# bottom_board.net
KiCad netlist of a schematic drawn in Altium Designer
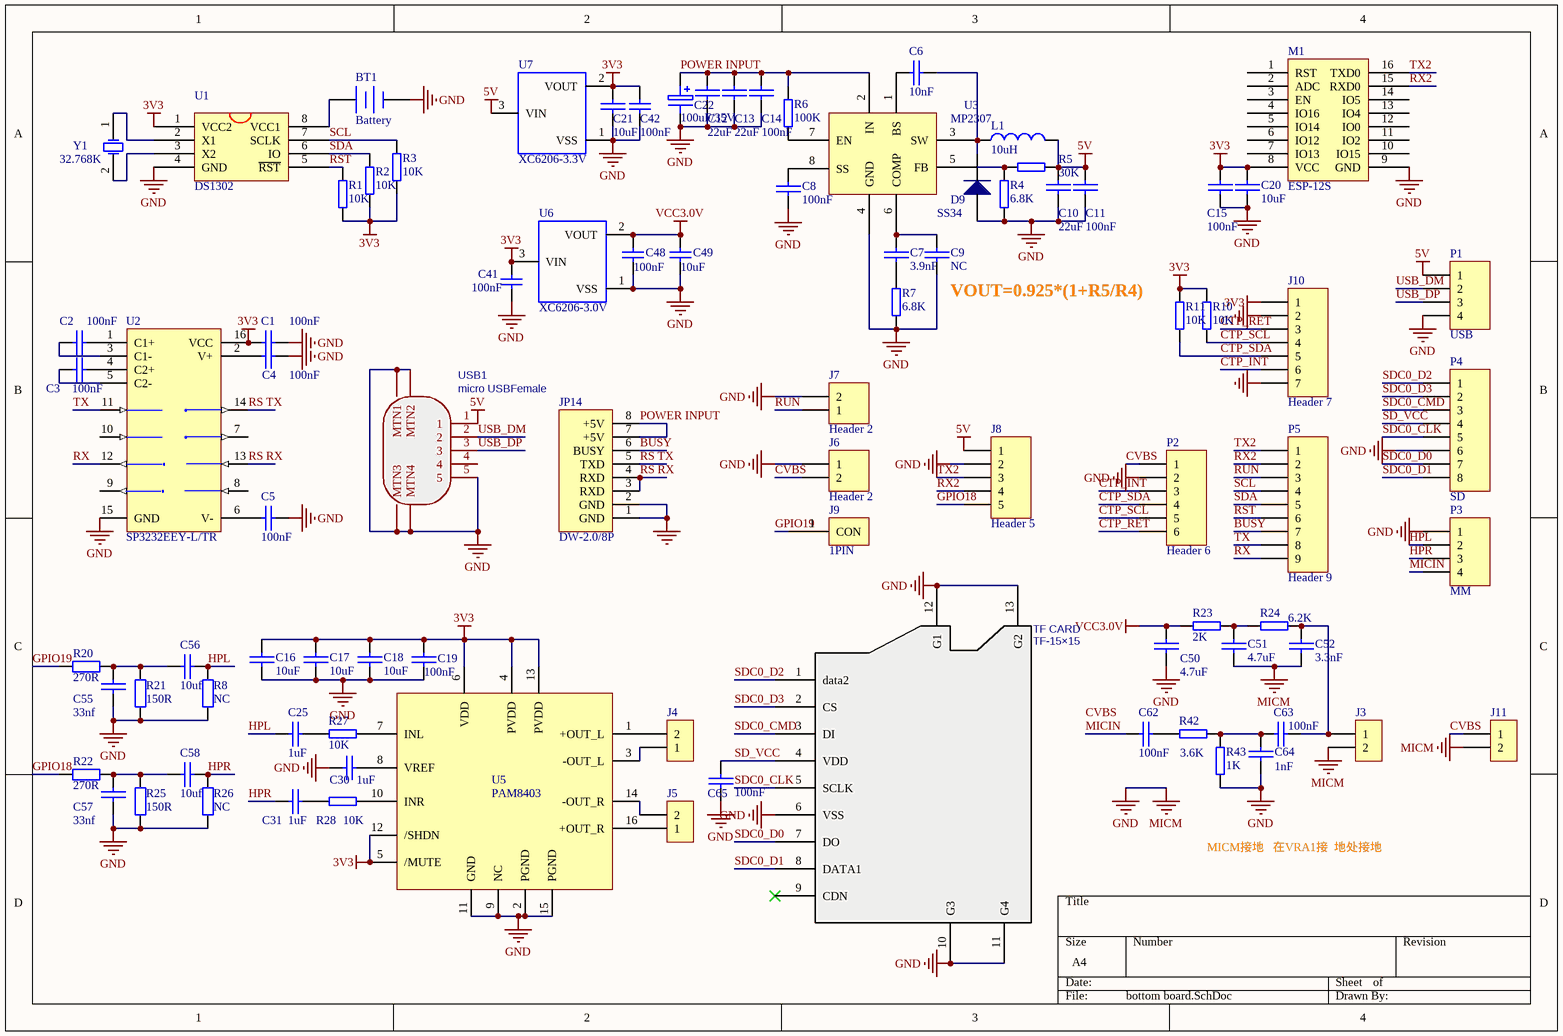
[diagram p0: bottom board.SchDoc]

(export (version "E")
  (design (tool "Eeschema 10.0.6"))
  (components
    (comp (ref "BT1")
      (value "Battery")
      (footprint "My Library:CR1220")
      (description "Multicell Battery")
      (fields (field (name "PUBLISHER") "Altium Limited"))
      (libsource (lib "Miscellaneous Devices") (part "Battery"))
    )
    (comp (ref "C1")
      (value "100nF")
      (footprint "My Library:0603")
      (description "Capacitor")
      (libsource (lib "Devices") (part "CAP"))
    )
    (comp (ref "C2")
      (value "100nF")
      (footprint "My Library:0603")
      (description "Capacitor")
      (libsource (lib "Devices") (part "CAP"))
    )
    (comp (ref "C3")
      (value "100nF")
      (footprint "My Library:0603")
      (description "Capacitor")
      (libsource (lib "Devices") (part "CAP"))
    )
    (comp (ref "C4")
      (value "100nF")
      (footprint "My Library:0603")
      (description "Capacitor")
      (libsource (lib "Devices") (part "CAP"))
    )
    (comp (ref "C5")
      (value "100nF")
      (footprint "My Library:0603")
      (description "Capacitor")
      (libsource (lib "Devices") (part "CAP"))
    )
    (comp (ref "C6")
      (value "10nF")
      (footprint "My Library:0805")
      (description "Capacitor")
      (libsource (lib "Devices") (part "CAP"))
    )
    (comp (ref "C7")
      (value "3.9nF")
      (footprint "My Library:0603")
      (description "Capacitor")
      (libsource (lib "Devices") (part "CAP"))
    )
    (comp (ref "C8")
      (value "100nF")
      (footprint "My Library:0603")
      (description "Capacitor")
      (libsource (lib "Devices") (part "CAP"))
    )
    (comp (ref "C9")
      (value "NC")
      (footprint "My Library:0603")
      (description "Capacitor")
      (libsource (lib "Devices") (part "CAP"))
    )
    (comp (ref "C10")
      (value "22uF")
      (footprint "My Library:0805")
      (description "Capacitor")
      (libsource (lib "Devices") (part "CAP"))
    )
    (comp (ref "C11")
      (value "100nF")
      (footprint "My Library:0603")
      (description "Capacitor")
      (libsource (lib "Devices") (part "CAP"))
    )
    (comp (ref "C12")
      (value "22uF")
      (footprint "My Library:0805")
      (description "Capacitor")
      (libsource (lib "Devices") (part "CAP"))
    )
    (comp (ref "C13")
      (value "22uF")
      (footprint "My Library:0805")
      (description "Capacitor")
      (libsource (lib "Devices") (part "CAP"))
    )
    (comp (ref "C14")
      (value "100nF")
      (footprint "My Library:0603")
      (description "Capacitor")
      (libsource (lib "Devices") (part "CAP"))
    )
    (comp (ref "C15")
      (value "100nF")
      (footprint "My Library:0603")
      (description "Capacitor")
      (libsource (lib "Devices") (part "CAP"))
    )
    (comp (ref "C16")
      (value "10uF")
      (footprint "0603")
      (description "Capacitor")
      (libsource (lib "Devices") (part "CAP"))
    )
    (comp (ref "C17")
      (value "10uF")
      (footprint "0603")
      (description "Capacitor")
      (libsource (lib "Devices") (part "CAP"))
    )
    (comp (ref "C18")
      (value "10uF")
      (footprint "My Library:0603")
      (description "Capacitor")
      (libsource (lib "Devices") (part "CAP"))
    )
    (comp (ref "C19")
      (value "100nF")
      (footprint "My Library:0603")
      (description "Capacitor")
      (libsource (lib "Devices") (part "CAP"))
    )
    (comp (ref "C20")
      (value "10uF")
      (footprint "My Library:0603")
      (description "Capacitor")
      (libsource (lib "Devices") (part "CAP"))
    )
    (comp (ref "C21")
      (value "10uF")
      (footprint "My Library:0603")
      (description "Capacitor")
      (libsource (lib "Devices") (part "CAP"))
    )
    (comp (ref "C22")
      (value "100uF/35V")
      (footprint "My Library:CAP_SMD_6.5MM")
      (libsource (lib "*") (part "ELECTRO1_W"))
    )
    (comp (ref "C25")
      (value "1uF")
      (footprint "My Library:0603")
      (description "Capacitor")
      (libsource (lib "Devices") (part "CAP"))
    )
    (comp (ref "C30")
      (value "1uF")
      (footprint "My Library:0603")
      (description "Capacitor")
      (libsource (lib "Devices") (part "CAP"))
    )
    (comp (ref "C31")
      (value "1uF")
      (footprint "My Library:0603")
      (description "Capacitor")
      (libsource (lib "Devices") (part "CAP"))
    )
    (comp (ref "C41")
      (value "100nF")
      (footprint "0603")
      (description "Capacitor")
      (fields (field (name "PUBLISHER") "Altium Limited"))
      (libsource (lib "Miscellaneous Devices") (part "Cap"))
    )
    (comp (ref "C42")
      (value "100nF")
      (footprint "0603")
      (description "Capacitor")
      (fields (field (name "PUBLISHER") "Altium Limited"))
      (libsource (lib "Miscellaneous Devices") (part "Cap"))
    )
    (comp (ref "C48")
      (value "100nF")
      (footprint "0603")
      (description "Capacitor")
      (fields (field (name "PUBLISHER") "Altium Limited"))
      (libsource (lib "Miscellaneous Devices") (part "Cap"))
    )
    (comp (ref "C49")
      (value "10uF")
      (footprint "0603")
      (description "Capacitor")
      (fields (field (name "PUBLISHER") "Altium Limited"))
      (libsource (lib "Miscellaneous Devices") (part "Cap"))
    )
    (comp (ref "C50")
      (value "4.7uF")
      (footprint "My Library:0603")
      (description "Capacitor")
      (libsource (lib "Devices") (part "CAP"))
    )
    (comp (ref "C51")
      (value "4.7uF")
      (footprint "My Library:0603")
      (description "Capacitor")
      (libsource (lib "Devices") (part "CAP"))
    )
    (comp (ref "C52")
      (value "3.3nF")
      (footprint "My Library:0603")
      (description "Capacitor")
      (libsource (lib "Devices") (part "CAP"))
    )
    (comp (ref "C55") (value "33nf") (footprint "0603") (libsource (lib "*") (part "CAP_W")))
    (comp (ref "C56") (value "10uf") (footprint "0603") (libsource (lib "") (part "CAP_W_1")))
    (comp (ref "C57") (value "33nf") (footprint "0603") (libsource (lib "*") (part "CAP_W")))
    (comp (ref "C58") (value "10uf") (footprint "0603") (libsource (lib "") (part "CAP_W_1")))
    (comp (ref "C62")
      (value "100nF")
      (footprint "My Library:0603")
      (description "Capacitor")
      (libsource (lib "Devices") (part "CAP"))
    )
    (comp (ref "C63")
      (value "100nF")
      (footprint "0603")
      (description "Capacitor")
      (libsource (lib "Devices") (part "CAP"))
    )
    (comp (ref "C64")
      (value "1nF")
      (footprint "My Library:0603")
      (description "Capacitor")
      (libsource (lib "Devices") (part "CAP"))
    )
    (comp (ref "C65")
      (value "100nF")
      (footprint "My Library:0603")
      (description "Capacitor")
      (libsource (lib "Devices") (part "CAP"))
    )
    (comp (ref "D9")
      (value "SS34")
      (footprint "My Library:SMA")
      (description "Diode")
      (libsource (lib "SchlibNode") (part "Diode"))
    )
    (comp (ref "J3")
      (value "~")
      (footprint "My Library:2PIN2.54-SMD")
      (description "Connector")
      (libsource (lib "") (part "CON2_1"))
    )
    (comp (ref "J4")
      (value "~")
      (footprint "My Library:2PIN2.54-SMD")
      (description "Connector")
      (libsource (lib "Devices") (part "CON2"))
    )
    (comp (ref "J5")
      (value "~")
      (footprint "My Library:2PIN2.54-SMD")
      (description "Connector")
      (libsource (lib "Devices") (part "CON2"))
    )
    (comp (ref "J6")
      (value "Header 2")
      (footprint "HDR1X2")
      (description "Header, 2-Pin")
      (fields (field (name "PUBLISHER") "Altium Limited"))
      (libsource (lib "Miscellaneous Connectors") (part "Header 2"))
    )
    (comp (ref "J7")
      (value "Header 2")
      (footprint "HDR1X2")
      (description "Header, 2-Pin")
      (fields (field (name "PUBLISHER") "Altium Limited"))
      (libsource (lib "") (part "Header 2_1"))
    )
    (comp (ref "J8")
      (value "Header 5")
      (footprint "HDR1X5")
      (description "Header, 5-Pin")
      (fields (field (name "PUBLISHER") "Altium Limited"))
      (libsource (lib "Miscellaneous Connectors") (part "Header 5"))
    )
    (comp (ref "J9")
      (value "1PIN")
      (footprint "My Library:1PIN")
      (libsource (lib "My Library") (part "1PIN"))
    )
    (comp (ref "J10")
      (value "Header 7")
      (footprint "My Library:FPC-6PIN")
      (description "Header, 7-Pin")
      (fields (field (name "PUBLISHER") "Altium Limited"))
      (libsource (lib "Miscellaneous Connectors") (part "Header 7"))
    )
    (comp (ref "J11")
      (value "~")
      (footprint "My Library:2PIN2.54-SMD")
      (description "Connector")
      (libsource (lib "") (part "CON2_1"))
    )
    (comp (ref "JP14")
      (value "DW-2.0/8P")
      (footprint "My Library:DW2.0-8P-SMD")
      (libsource (lib "Socket") (part "DW-2.0/8P"))
    )
    (comp (ref "L1")
      (value "10uH")
      (footprint "My Library:LS8")
      (description "Inductor")
      (fields (field (name "PUBLISHER") "Altium Limited"))
      (libsource (lib "Miscellaneous Devices") (part "Inductor"))
    )
    (comp (ref "M1")
      (value "ESP-12S")
      (footprint "My Library:ESP-12S")
      (libsource (lib "My Library") (part "ESP-12S"))
    )
    (comp (ref "P1")
      (value "USB")
      (footprint "My Library:4PIN1.27")
      (description "Header, 4-Pin")
      (fields (field (name "PUBLISHER") "Altium Limited"))
      (libsource (lib "Miscellaneous Connectors") (part "Header 4"))
    )
    (comp (ref "P2")
      (value "Header 6")
      (footprint "My Library:6PIN1.27")
      (description "Header, 6-Pin")
      (fields (field (name "PUBLISHER") "Altium Limited"))
      (libsource (lib "Miscellaneous Connectors") (part "Header 6"))
    )
    (comp (ref "P3")
      (value "MM")
      (footprint "My Library:4PIN1.27")
      (description "Header, 4-Pin")
      (fields (field (name "PUBLISHER") "Altium Limited"))
      (libsource (lib "Miscellaneous Connectors") (part "Header 4"))
    )
    (comp (ref "P4")
      (value "SD")
      (footprint "My Library:8PIN1.27")
      (description "Header, 8-Pin")
      (fields (field (name "PUBLISHER") "Altium Limited"))
      (libsource (lib "Miscellaneous Connectors") (part "Header 8"))
    )
    (comp (ref "P5")
      (value "Header 9")
      (footprint "My Library:9PIN1.27")
      (description "Header, 9-Pin")
      (fields (field (name "PUBLISHER") "Altium Limited"))
      (libsource (lib "Miscellaneous Connectors") (part "Header 9"))
    )
    (comp (ref "R1") (value "10K") (footprint "0603") (libsource (lib "Devices") (part "RES2")))
    (comp (ref "R2") (value "10K") (footprint "0603") (libsource (lib "Devices") (part "RES2")))
    (comp (ref "R3") (value "10K") (footprint "0603") (libsource (lib "Devices") (part "RES2")))
    (comp (ref "R4") (value "6.8K") (footprint "0603") (libsource (lib "Devices") (part "RES2")))
    (comp (ref "R5") (value "30K") (footprint "0603") (libsource (lib "") (part "RES2_1")))
    (comp (ref "R6") (value "100K") (footprint "0603") (libsource (lib "Devices") (part "RES2")))
    (comp (ref "R7") (value "6.8K") (footprint "0603") (libsource (lib "Devices") (part "RES2")))
    (comp (ref "R8")
      (value "NC")
      (footprint "My Library:0603")
      (description "Resistor")
      (fields (field (name "PUBLISHER") "Altium Limited"))
      (libsource (lib "Miscellaneous Devices") (part "Res2"))
    )
    (comp (ref "R10") (value "10K") (footprint "0603") (libsource (lib "Devices") (part "RES2")))
    (comp (ref "R11") (value "10K") (footprint "0603") (libsource (lib "Devices") (part "RES2")))
    (comp (ref "R20")
      (value "270R")
      (footprint "My Library:0603")
      (description "Resistor")
      (fields (field (name "PUBLISHER") "Altium Limited"))
      (libsource (lib "") (part "Res2_1"))
    )
    (comp (ref "R21")
      (value "150R")
      (footprint "My Library:0603")
      (description "Resistor")
      (fields (field (name "PUBLISHER") "Altium Limited"))
      (libsource (lib "") (part "Res2_2"))
    )
    (comp (ref "R22")
      (value "270R")
      (footprint "My Library:0603")
      (description "Resistor")
      (fields (field (name "PUBLISHER") "Altium Limited"))
      (libsource (lib "") (part "Res2_3"))
    )
    (comp (ref "R23") (value "2K") (footprint "0603") (libsource (lib "") (part "RES2_1")))
    (comp (ref "R24") (value "6.2K") (footprint "0603") (libsource (lib "") (part "RES2_1")))
    (comp (ref "R25")
      (value "150R")
      (footprint "My Library:0603")
      (description "Resistor")
      (fields (field (name "PUBLISHER") "Altium Limited"))
      (libsource (lib "Miscellaneous Devices") (part "Res2"))
    )
    (comp (ref "R26")
      (value "NC")
      (footprint "My Library:0603")
      (description "Resistor")
      (fields (field (name "PUBLISHER") "Altium Limited"))
      (libsource (lib "Miscellaneous Devices") (part "Res2"))
    )
    (comp (ref "R27") (value "10K") (footprint "0603") (libsource (lib "Devices") (part "RES2")))
    (comp (ref "R28") (value "10K") (footprint "0603") (libsource (lib "Devices") (part "RES2")))
    (comp (ref "R42") (value "3.6K") (footprint "0603") (libsource (lib "Devices") (part "RES2")))
    (comp (ref "R43") (value "1K") (footprint "0603") (libsource (lib "Devices") (part "RES2")))
    (comp (ref "TF CARD")
      (value "TF-15×15")
      (footprint "My Library:SD_MICRO")
      (fields (field (name "BOM_SUPPLIER PART") "C111196"))
      (libsource (lib "My Library") (part "TF-15×15"))
    )
    (comp (ref "U1") (value "DS1302") (footprint "SOP-8") (libsource (lib "My Library") (part "DS1302")))
    (comp (ref "U2")
      (value "SP3232EEY-L/TR")
      (footprint "My Library:SOIC-16")
      (description "RS232")
      (libsource (lib "IC") (part "SP3232EEY-L/TR"))
    )
    (comp (ref "U3")
      (value "MP2307")
      (footprint "My Library:SOP-8")
      (libsource (lib "My Library") (part "MP2307"))
    )
    (comp (ref "U5") (value "PAM8403") (footprint "SOIC-16") (libsource (lib "Devices") (part "SC8403")))
    (comp (ref "U6") (value "XC6206-3.0V") (footprint "SOT-23-3") (libsource (lib "PCBLIB") (part "XC6206")))
    (comp (ref "U7") (value "XC6206-3.3V") (footprint "SOT-23-3") (libsource (lib "PCBLIB") (part "XC6206")))
    (comp (ref "USB1")
      (value "micro USBFemale")
      (footprint "USB_MICRO")
      (fields (field (name "BOM_SUPPLIER PART") "C10418"))
      (libsource (lib "My Library") (part "micro USBFemale"))
    )
    (comp (ref "Y1")
      (value "32.768K")
      (footprint "My Library:SMD-3215")
      (description "Crystal Oscillator")
      (fields (field (name "PUBLISHER") "Altium Limited"))
      (libsource (lib "Miscellaneous Devices") (part "XTAL"))
    )
  )
  (nets
    (net (code "1") (name "/BUSY") (class "Default")
      (node (ref "JP14") (pin "6") (pinfunction "BUSY_6") (pintype "passive"))
      (node (ref "P5") (pin "7") (pinfunction "7_7") (pintype "passive"))
    )
    (net (code "2") (name "/CTP_INT") (class "Default")
      (node (ref "J10") (pin "6") (pinfunction "6_6") (pintype "passive"))
      (node (ref "P2") (pin "3") (pinfunction "3_3") (pintype "passive"))
    )
    (net (code "3") (name "/CTP_RET") (class "Default")
      (node (ref "J10") (pin "3") (pinfunction "3_3") (pintype "passive"))
      (node (ref "P2") (pin "6") (pinfunction "6_6") (pintype "passive"))
    )
    (net (code "4") (name "/CTP_SCL") (class "Default")
      (node (ref "J10") (pin "4") (pinfunction "4_4") (pintype "passive"))
      (node (ref "P2") (pin "5") (pinfunction "5_5") (pintype "passive"))
      (node (ref "R10") (pin "2") (pinfunction "2_2") (pintype "passive"))
    )
    (net (code "5") (name "/CTP_SDA") (class "Default")
      (node (ref "J10") (pin "5") (pinfunction "5_5") (pintype "passive"))
      (node (ref "P2") (pin "4") (pinfunction "4_4") (pintype "passive"))
      (node (ref "R11") (pin "2") (pinfunction "2_2") (pintype "passive"))
    )
    (net (code "6") (name "/CVBS") (class "Default")
      (node (ref "J11") (pin "1") (pinfunction "1_1") (pintype "passive"))
      (node (ref "J6") (pin "2") (pinfunction "2_2") (pintype "passive"))
      (node (ref "P2") (pin "1") (pinfunction "1_1") (pintype "passive"))
    )
    (net (code "7") (name "/GPIO18") (class "Default")
      (node (ref "J8") (pin "5") (pinfunction "5_5") (pintype "passive"))
      (node (ref "R22") (pin "1") (pinfunction "1_1") (pintype "passive"))
    )
    (net (code "8") (name "/GPIO19") (class "Default")
      (node (ref "J9") (pin "1") (pinfunction "CON_1") (pintype "passive"))
      (node (ref "R20") (pin "2") (pinfunction "2_2") (pintype "passive"))
    )
    (net (code "9") (name "/HPL") (class "Default")
      (node (ref "C25") (pin "2") (pinfunction "2_2") (pintype "passive"))
      (node (ref "C56") (pin "1") (pinfunction "1_1") (pintype "passive"))
      (node (ref "P3") (pin "2") (pinfunction "2_2") (pintype "passive"))
      (node (ref "R8") (pin "2") (pinfunction "2_2") (pintype "passive"))
    )
    (net (code "10") (name "/HPR") (class "Default")
      (node (ref "C31") (pin "2") (pinfunction "2_2") (pintype "passive"))
      (node (ref "C58") (pin "1") (pinfunction "1_1") (pintype "passive"))
      (node (ref "P3") (pin "3") (pinfunction "3_3") (pintype "passive"))
      (node (ref "R26") (pin "2") (pinfunction "2_2") (pintype "passive"))
    )
    (net (code "11") (name "/MICIN") (class "Default")
      (node (ref "C62") (pin "1") (pinfunction "1_1") (pintype "passive"))
      (node (ref "P3") (pin "4") (pinfunction "4_4") (pintype "passive"))
    )
    (net (code "12") (name "/POWER INPUT") (class "Default")
      (node (ref "C12") (pin "1") (pinfunction "1_1") (pintype "passive"))
      (node (ref "C13") (pin "1") (pinfunction "1_1") (pintype "passive"))
      (node (ref "C14") (pin "1") (pinfunction "1_1") (pintype "passive"))
      (node (ref "C22") (pin "1") (pinfunction "1_1") (pintype "passive"))
      (node (ref "JP14") (pin "7") (pinfunction "+5V_7") (pintype "passive"))
      (node (ref "JP14") (pin "8") (pinfunction "+5V_8") (pintype "passive"))
      (node (ref "R6") (pin "2") (pinfunction "2_2") (pintype "passive"))
      (node (ref "U3") (pin "2") (pinfunction "IN_2") (pintype "passive"))
    )
    (net (code "13") (name "/RS RX") (class "Default")
      (node (ref "JP14") (pin "3") (pinfunction "RXD_3") (pintype "passive"))
      (node (ref "JP14") (pin "4") (pinfunction "RXD_4") (pintype "passive"))
      (node (ref "U2") (pin "13") (pinfunction "R1IN_13") (pintype "input"))
    )
    (net (code "14") (name "/RS TX") (class "Default")
      (node (ref "JP14") (pin "5") (pinfunction "TXD_5") (pintype "passive"))
      (node (ref "U2") (pin "14") (pinfunction "T1OUT_14") (pintype "output"))
    )
    (net (code "15") (name "/RST") (class "Default")
      (node (ref "P5") (pin "6") (pinfunction "6_6") (pintype "passive"))
      (node (ref "R1") (pin "2") (pinfunction "2_2") (pintype "passive"))
      (node (ref "U1") (pin "5") (pinfunction "~{RST}_5") (pintype "passive"))
    )
    (net (code "16") (name "/RUN") (class "Default")
      (node (ref "J7") (pin "1") (pinfunction "1_1") (pintype "passive"))
      (node (ref "P5") (pin "3") (pinfunction "3_3") (pintype "passive"))
    )
    (net (code "17") (name "/RX") (class "Default")
      (node (ref "P5") (pin "9") (pinfunction "9_9") (pintype "passive"))
      (node (ref "U2") (pin "12") (pinfunction "R1OUT_12") (pintype "output"))
    )
    (net (code "18") (name "/RX2") (class "Default")
      (node (ref "J8") (pin "4") (pinfunction "4_4") (pintype "passive"))
      (node (ref "M1") (pin "15") (pinfunction "RXD0_15") (pintype "passive"))
      (node (ref "P5") (pin "2") (pinfunction "2_2") (pintype "passive"))
    )
    (net (code "19") (name "/SCL") (class "Default")
      (node (ref "P5") (pin "4") (pinfunction "4_4") (pintype "passive"))
      (node (ref "R3") (pin "1") (pinfunction "1_1") (pintype "passive"))
      (node (ref "U1") (pin "7") (pinfunction "SCLK_7") (pintype "passive"))
    )
    (net (code "20") (name "/SDA") (class "Default")
      (node (ref "P5") (pin "5") (pinfunction "5_5") (pintype "passive"))
      (node (ref "R2") (pin "1") (pinfunction "1_1") (pintype "passive"))
      (node (ref "U1") (pin "6") (pinfunction "IO_6") (pintype "passive"))
    )
    (net (code "21") (name "/SDC0_CLK") (class "Default")
      (node (ref "P4") (pin "5") (pinfunction "5_5") (pintype "passive"))
      (node (ref "TF CARD") (pin "5") (pinfunction "SCLK_5") (pintype "passive"))
    )
    (net (code "22") (name "/SDC0_CMD") (class "Default")
      (node (ref "P4") (pin "3") (pinfunction "3_3") (pintype "passive"))
      (node (ref "TF CARD") (pin "3") (pinfunction "DI_3") (pintype "passive"))
    )
    (net (code "23") (name "/SDC0_D0") (class "Default")
      (node (ref "P4") (pin "7") (pinfunction "7_7") (pintype "passive"))
      (node (ref "TF CARD") (pin "7") (pinfunction "DO_7") (pintype "passive"))
    )
    (net (code "24") (name "/SDC0_D1") (class "Default")
      (node (ref "P4") (pin "8") (pinfunction "8_8") (pintype "passive"))
      (node (ref "TF CARD") (pin "8") (pinfunction "DATA1_8") (pintype "passive"))
    )
    (net (code "25") (name "/SDC0_D2") (class "Default")
      (node (ref "P4") (pin "1") (pinfunction "1_1") (pintype "passive"))
      (node (ref "TF CARD") (pin "1") (pinfunction "data2_1") (pintype "passive"))
    )
    (net (code "26") (name "/SDC0_D3") (class "Default")
      (node (ref "P4") (pin "2") (pinfunction "2_2") (pintype "passive"))
      (node (ref "TF CARD") (pin "2") (pinfunction "CS_2") (pintype "passive"))
    )
    (net (code "27") (name "/SD_VCC") (class "Default")
      (node (ref "C65") (pin "1") (pinfunction "1_1") (pintype "passive"))
      (node (ref "P4") (pin "4") (pinfunction "4_4") (pintype "passive"))
      (node (ref "TF CARD") (pin "4") (pinfunction "VDD_4") (pintype "passive"))
    )
    (net (code "28") (name "/TX") (class "Default")
      (node (ref "P5") (pin "8") (pinfunction "8_8") (pintype "passive"))
      (node (ref "U2") (pin "11") (pinfunction "T1IN_11") (pintype "input"))
    )
    (net (code "29") (name "/TX2") (class "Default")
      (node (ref "J8") (pin "3") (pinfunction "3_3") (pintype "passive"))
      (node (ref "M1") (pin "16") (pinfunction "TXD0_16") (pintype "passive"))
      (node (ref "P5") (pin "1") (pinfunction "1_1") (pintype "passive"))
    )
    (net (code "30") (name "/USB_DM") (class "Default")
      (node (ref "P1") (pin "2") (pinfunction "2_2") (pintype "passive"))
      (node (ref "USB1") (pin "2") (pinfunction "2_2") (pintype "passive"))
    )
    (net (code "31") (name "/USB_DP") (class "Default")
      (node (ref "P1") (pin "3") (pinfunction "3_3") (pintype "passive"))
      (node (ref "USB1") (pin "3") (pinfunction "3_3") (pintype "passive"))
    )
    (net (code "32") (name "3V3") (class "Default")
      (node (ref "C1") (pin "2") (pinfunction "2_2") (pintype "passive"))
      (node (ref "C15") (pin "1") (pinfunction "1_1") (pintype "passive"))
      (node (ref "C16") (pin "1") (pinfunction "1_1") (pintype "passive"))
      (node (ref "C17") (pin "1") (pinfunction "1_1") (pintype "passive"))
      (node (ref "C18") (pin "1") (pinfunction "1_1") (pintype "passive"))
      (node (ref "C19") (pin "2") (pinfunction "2_2") (pintype "passive"))
      (node (ref "C20") (pin "2") (pinfunction "2_2") (pintype "passive"))
      (node (ref "C21") (pin "1") (pinfunction "1_1") (pintype "passive"))
      (node (ref "C41") (pin "1") (pinfunction "1_1") (pintype "passive"))
      (node (ref "C42") (pin "1") (pinfunction "1_1") (pintype "passive"))
      (node (ref "J10") (pin "1") (pinfunction "1_1") (pintype "passive"))
      (node (ref "M1") (pin "8") (pinfunction "VCC_8") (pintype "passive"))
      (node (ref "R1") (pin "1") (pinfunction "1_1") (pintype "passive"))
      (node (ref "R10") (pin "1") (pinfunction "1_1") (pintype "passive"))
      (node (ref "R11") (pin "1") (pinfunction "1_1") (pintype "passive"))
      (node (ref "R2") (pin "2") (pinfunction "2_2") (pintype "passive"))
      (node (ref "R3") (pin "2") (pinfunction "2_2") (pintype "passive"))
      (node (ref "U1") (pin "1") (pinfunction "VCC2_1") (pintype "passive"))
      (node (ref "U2") (pin "16") (pinfunction "VCC_16") (pintype "power_in"))
      (node (ref "U5") (pin "12") (pinfunction "/SHDN_12") (pintype "passive"))
      (node (ref "U5") (pin "13") (pinfunction "PVDD_13") (pintype "passive"))
      (node (ref "U5") (pin "4") (pinfunction "PVDD_4") (pintype "passive"))
      (node (ref "U5") (pin "5") (pinfunction "/MUTE_5") (pintype "passive"))
      (node (ref "U5") (pin "6") (pinfunction "VDD_6") (pintype "passive"))
      (node (ref "U6") (pin "3") (pinfunction "VIN_3") (pintype "passive"))
      (node (ref "U7") (pin "2") (pinfunction "VOUT_2") (pintype "passive"))
    )
    (net (code "33") (name "5V") (class "Default")
      (node (ref "C10") (pin "1") (pinfunction "1_1") (pintype "passive"))
      (node (ref "C11") (pin "1") (pinfunction "1_1") (pintype "passive"))
      (node (ref "J8") (pin "1") (pinfunction "1_1") (pintype "passive"))
      (node (ref "L1") (pin "2") (pinfunction "2_2") (pintype "passive"))
      (node (ref "P1") (pin "1") (pinfunction "1_1") (pintype "passive"))
      (node (ref "R5") (pin "2") (pinfunction "2_2") (pintype "passive"))
      (node (ref "U7") (pin "3") (pinfunction "VIN_3") (pintype "passive"))
      (node (ref "USB1") (pin "1") (pinfunction "1_1") (pintype "passive"))
    )
    (net (code "34") (name "GND") (class "Default")
      (node (ref "BT1") (pin "2") (pinfunction "-_2") (pintype "passive"))
      (node (ref "C1") (pin "1") (pinfunction "1_1") (pintype "passive"))
      (node (ref "C10") (pin "2") (pinfunction "2_2") (pintype "passive"))
      (node (ref "C11") (pin "2") (pinfunction "2_2") (pintype "passive"))
      (node (ref "C12") (pin "2") (pinfunction "2_2") (pintype "passive"))
      (node (ref "C13") (pin "2") (pinfunction "2_2") (pintype "passive"))
      (node (ref "C14") (pin "2") (pinfunction "2_2") (pintype "passive"))
      (node (ref "C15") (pin "2") (pinfunction "2_2") (pintype "passive"))
      (node (ref "C16") (pin "2") (pinfunction "2_2") (pintype "passive"))
      (node (ref "C17") (pin "2") (pinfunction "2_2") (pintype "passive"))
      (node (ref "C18") (pin "2") (pinfunction "2_2") (pintype "passive"))
      (node (ref "C19") (pin "1") (pinfunction "1_1") (pintype "passive"))
      (node (ref "C20") (pin "1") (pinfunction "1_1") (pintype "passive"))
      (node (ref "C21") (pin "2") (pinfunction "2_2") (pintype "passive"))
      (node (ref "C22") (pin "2") (pinfunction "2_2") (pintype "passive"))
      (node (ref "C30") (pin "2") (pinfunction "2_2") (pintype "passive"))
      (node (ref "C4") (pin "2") (pinfunction "2_2") (pintype "passive"))
      (node (ref "C41") (pin "2") (pinfunction "2_2") (pintype "passive"))
      (node (ref "C42") (pin "2") (pinfunction "2_2") (pintype "passive"))
      (node (ref "C48") (pin "2") (pinfunction "2_2") (pintype "passive"))
      (node (ref "C49") (pin "1") (pinfunction "1_1") (pintype "passive"))
      (node (ref "C5") (pin "1") (pinfunction "1_1") (pintype "passive"))
      (node (ref "C50") (pin "2") (pinfunction "2_2") (pintype "passive"))
      (node (ref "C51") (pin "2") (pinfunction "2_2") (pintype "passive"))
      (node (ref "C52") (pin "1") (pinfunction "1_1") (pintype "passive"))
      (node (ref "C55") (pin "1") (pinfunction "1_1") (pintype "passive"))
      (node (ref "C57") (pin "1") (pinfunction "1_1") (pintype "passive"))
      (node (ref "C64") (pin "1") (pinfunction "1_1") (pintype "passive"))
      (node (ref "C65") (pin "2") (pinfunction "2_2") (pintype "passive"))
      (node (ref "C8") (pin "2") (pinfunction "2_2") (pintype "passive"))
      (node (ref "C9") (pin "2") (pinfunction "2_2") (pintype "passive"))
      (node (ref "D9") (pin "1") (pinfunction "A_1") (pintype "passive"))
      (node (ref "J10") (pin "2") (pinfunction "2_2") (pintype "passive"))
      (node (ref "J10") (pin "7") (pinfunction "7_7") (pintype "passive"))
      (node (ref "J11") (pin "2") (pinfunction "2_2") (pintype "passive"))
      (node (ref "J3") (pin "2") (pinfunction "2_2") (pintype "passive"))
      (node (ref "J6") (pin "1") (pinfunction "1_1") (pintype "passive"))
      (node (ref "J7") (pin "2") (pinfunction "2_2") (pintype "passive"))
      (node (ref "J8") (pin "2") (pinfunction "2_2") (pintype "passive"))
      (node (ref "JP14") (pin "1") (pinfunction "GND_1") (pintype "passive"))
      (node (ref "JP14") (pin "2") (pinfunction "GND_2") (pintype "passive"))
      (node (ref "M1") (pin "9") (pinfunction "GND_9") (pintype "passive"))
      (node (ref "P1") (pin "4") (pinfunction "4_4") (pintype "passive"))
      (node (ref "P2") (pin "2") (pinfunction "2_2") (pintype "passive"))
      (node (ref "P3") (pin "1") (pinfunction "1_1") (pintype "passive"))
      (node (ref "P4") (pin "6") (pinfunction "6_6") (pintype "passive"))
      (node (ref "R21") (pin "2") (pinfunction "2_2") (pintype "passive"))
      (node (ref "R25") (pin "1") (pinfunction "1_1") (pintype "passive"))
      (node (ref "R26") (pin "1") (pinfunction "1_1") (pintype "passive"))
      (node (ref "R4") (pin "2") (pinfunction "2_2") (pintype "passive"))
      (node (ref "R43") (pin "1") (pinfunction "1_1") (pintype "passive"))
      (node (ref "R7") (pin "1") (pinfunction "1_1") (pintype "passive"))
      (node (ref "R8") (pin "1") (pinfunction "1_1") (pintype "passive"))
      (node (ref "TF CARD") (pin "10") (pinfunction "G3_10") (pintype "passive"))
      (node (ref "TF CARD") (pin "11") (pinfunction "G4_11") (pintype "passive"))
      (node (ref "TF CARD") (pin "12") (pinfunction "G1_12") (pintype "passive"))
      (node (ref "TF CARD") (pin "13") (pinfunction "G2_13") (pintype "passive"))
      (node (ref "TF CARD") (pin "6") (pinfunction "VSS_6") (pintype "passive"))
      (node (ref "U1") (pin "4") (pinfunction "GND_4") (pintype "passive"))
      (node (ref "U2") (pin "15") (pinfunction "GND_15") (pintype "power_in"))
      (node (ref "U3") (pin "4") (pinfunction "GND_4") (pintype "passive"))
      (node (ref "U5") (pin "11") (pinfunction "GND_11") (pintype "passive"))
      (node (ref "U5") (pin "15") (pinfunction "PGND_15") (pintype "passive"))
      (node (ref "U5") (pin "2") (pinfunction "PGND_2") (pintype "passive"))
      (node (ref "U5") (pin "9") (pinfunction "NC_9") (pintype "passive"))
      (node (ref "U6") (pin "1") (pinfunction "VSS_1") (pintype "passive"))
      (node (ref "U7") (pin "1") (pinfunction "VSS_1") (pintype "passive"))
      (node (ref "USB1") (pin "0") (pinfunction "MTN4_0") (pintype "passive"))
      (node (ref "USB1") (pin "5") (pinfunction "5_5") (pintype "passive"))
    )
    (net (code "35") (name "Net-(BT1-+)") (class "Default")
      (node (ref "BT1") (pin "1") (pinfunction "+_1") (pintype "passive"))
      (node (ref "U1") (pin "8") (pinfunction "VCC1_8") (pintype "passive"))
    )
    (net (code "36") (name "Net-(C7-Pad2)") (class "Default")
      (node (ref "C7") (pin "2") (pinfunction "2_2") (pintype "passive"))
      (node (ref "R7") (pin "2") (pinfunction "2_2") (pintype "passive"))
    )
    (net (code "37") (name "Net-(C25-Pad1)") (class "Default")
      (node (ref "C25") (pin "1") (pinfunction "1_1") (pintype "passive"))
      (node (ref "R27") (pin "2") (pinfunction "2_2") (pintype "passive"))
    )
    (net (code "38") (name "Net-(C31-Pad1)") (class "Default")
      (node (ref "C31") (pin "1") (pinfunction "1_1") (pintype "passive"))
      (node (ref "R28") (pin "2") (pinfunction "2_2") (pintype "passive"))
    )
    (net (code "39") (name "Net-(C51-Pad1)") (class "Default")
      (node (ref "C51") (pin "1") (pinfunction "1_1") (pintype "passive"))
      (node (ref "R23") (pin "1") (pinfunction "1_1") (pintype "passive"))
      (node (ref "R24") (pin "2") (pinfunction "2_2") (pintype "passive"))
    )
    (net (code "40") (name "Net-(C52-Pad2)") (class "Default")
      (node (ref "C52") (pin "2") (pinfunction "2_2") (pintype "passive"))
      (node (ref "C63") (pin "2") (pinfunction "2_2") (pintype "passive"))
      (node (ref "J3") (pin "1") (pinfunction "1_1") (pintype "passive"))
      (node (ref "R24") (pin "1") (pinfunction "1_1") (pintype "passive"))
    )
    (net (code "41") (name "Net-(C55-Pad2)") (class "Default")
      (node (ref "C55") (pin "2") (pinfunction "2_2") (pintype "passive"))
      (node (ref "C56") (pin "2") (pinfunction "2_2") (pintype "passive"))
      (node (ref "R20") (pin "1") (pinfunction "1_1") (pintype "passive"))
      (node (ref "R21") (pin "1") (pinfunction "1_1") (pintype "passive"))
    )
    (net (code "42") (name "Net-(C57-Pad2)") (class "Default")
      (node (ref "C57") (pin "2") (pinfunction "2_2") (pintype "passive"))
      (node (ref "C58") (pin "2") (pinfunction "2_2") (pintype "passive"))
      (node (ref "R22") (pin "2") (pinfunction "2_2") (pintype "passive"))
      (node (ref "R25") (pin "2") (pinfunction "2_2") (pintype "passive"))
    )
    (net (code "43") (name "Net-(C62-Pad2)") (class "Default")
      (node (ref "C62") (pin "2") (pinfunction "2_2") (pintype "passive"))
      (node (ref "R42") (pin "1") (pinfunction "1_1") (pintype "passive"))
    )
    (net (code "44") (name "Net-(C63-Pad1)") (class "Default")
      (node (ref "C63") (pin "1") (pinfunction "1_1") (pintype "passive"))
      (node (ref "C64") (pin "2") (pinfunction "2_2") (pintype "passive"))
      (node (ref "R42") (pin "2") (pinfunction "2_2") (pintype "passive"))
      (node (ref "R43") (pin "2") (pinfunction "2_2") (pintype "passive"))
    )
    (net (code "45") (name "Net-(D9-K)") (class "Default")
      (node (ref "C6") (pin "1") (pinfunction "1_1") (pintype "passive"))
      (node (ref "D9") (pin "2") (pinfunction "K_2") (pintype "passive"))
      (node (ref "L1") (pin "1") (pinfunction "1_1") (pintype "passive"))
      (node (ref "U3") (pin "3") (pinfunction "SW_3") (pintype "passive"))
    )
    (net (code "46") (name "Net-(U1-X1)") (class "Default")
      (node (ref "U1") (pin "2") (pinfunction "X1_2") (pintype "passive"))
      (node (ref "Y1") (pin "1") (pinfunction "OSC1_1") (pintype "passive"))
    )
    (net (code "47") (name "Net-(U1-X2)") (class "Default")
      (node (ref "U1") (pin "3") (pinfunction "X2_3") (pintype "passive"))
      (node (ref "Y1") (pin "2") (pinfunction "OSC2_2") (pintype "passive"))
    )
    (net (code "48") (name "Net-(U2-C1+)") (class "Default")
      (node (ref "C2") (pin "1") (pinfunction "1_1") (pintype "passive"))
      (node (ref "U2") (pin "1") (pinfunction "C1+_1") (pintype "passive"))
    )
    (net (code "49") (name "Net-(U2-C1-)") (class "Default")
      (node (ref "C2") (pin "2") (pinfunction "2_2") (pintype "passive"))
      (node (ref "U2") (pin "3") (pinfunction "C1-_3") (pintype "passive"))
    )
    (net (code "50") (name "Net-(U2-C2+)") (class "Default")
      (node (ref "C3") (pin "1") (pinfunction "1_1") (pintype "passive"))
      (node (ref "U2") (pin "4") (pinfunction "C2+_4") (pintype "passive"))
    )
    (net (code "51") (name "Net-(U2-C2-)") (class "Default")
      (node (ref "C3") (pin "2") (pinfunction "2_2") (pintype "passive"))
      (node (ref "U2") (pin "5") (pinfunction "C2-_5") (pintype "passive"))
    )
    (net (code "52") (name "Net-(U2-V+)") (class "Default")
      (node (ref "C4") (pin "1") (pinfunction "1_1") (pintype "passive"))
      (node (ref "U2") (pin "2") (pinfunction "V+_2") (pintype "power_in"))
    )
    (net (code "53") (name "Net-(U2-V-)") (class "Default")
      (node (ref "C5") (pin "2") (pinfunction "2_2") (pintype "passive"))
      (node (ref "U2") (pin "6") (pinfunction "V-_6") (pintype "power_in"))
    )
    (net (code "54") (name "Net-(U3-BS)") (class "Default")
      (node (ref "C6") (pin "2") (pinfunction "2_2") (pintype "passive"))
      (node (ref "U3") (pin "1") (pinfunction "BS_1") (pintype "passive"))
    )
    (net (code "55") (name "Net-(U3-COMP)") (class "Default")
      (node (ref "C7") (pin "1") (pinfunction "1_1") (pintype "passive"))
      (node (ref "C9") (pin "1") (pinfunction "1_1") (pintype "passive"))
      (node (ref "U3") (pin "6") (pinfunction "COMP_6") (pintype "passive"))
    )
    (net (code "56") (name "Net-(U3-EN)") (class "Default")
      (node (ref "R6") (pin "1") (pinfunction "1_1") (pintype "passive"))
      (node (ref "U3") (pin "7") (pinfunction "EN_7") (pintype "passive"))
    )
    (net (code "57") (name "Net-(U3-FB)") (class "Default")
      (node (ref "R4") (pin "1") (pinfunction "1_1") (pintype "passive"))
      (node (ref "R5") (pin "1") (pinfunction "1_1") (pintype "passive"))
      (node (ref "U3") (pin "5") (pinfunction "FB_5") (pintype "passive"))
    )
    (net (code "58") (name "Net-(U3-SS)") (class "Default")
      (node (ref "C8") (pin "1") (pinfunction "1_1") (pintype "passive"))
      (node (ref "U3") (pin "8") (pinfunction "SS_8") (pintype "passive"))
    )
    (net (code "59") (name "Net-(U5-+OUT_L)") (class "Default")
      (node (ref "J4") (pin "2") (pinfunction "2_2") (pintype "passive"))
      (node (ref "U5") (pin "1") (pinfunction "+OUT_L_1") (pintype "passive"))
    )
    (net (code "60") (name "Net-(U5-+OUT_R)") (class "Default")
      (node (ref "J5") (pin "1") (pinfunction "1_1") (pintype "passive"))
      (node (ref "U5") (pin "16") (pinfunction "+OUT_R_16") (pintype "passive"))
    )
    (net (code "61") (name "Net-(U5--OUT_L)") (class "Default")
      (node (ref "J4") (pin "1") (pinfunction "1_1") (pintype "passive"))
      (node (ref "U5") (pin "3") (pinfunction "-OUT_L_3") (pintype "passive"))
    )
    (net (code "62") (name "Net-(U5--OUT_R)") (class "Default")
      (node (ref "J5") (pin "2") (pinfunction "2_2") (pintype "passive"))
      (node (ref "U5") (pin "14") (pinfunction "-OUT_R_14") (pintype "passive"))
    )
    (net (code "63") (name "Net-(U5-INL)") (class "Default")
      (node (ref "R27") (pin "1") (pinfunction "1_1") (pintype "passive"))
      (node (ref "U5") (pin "7") (pinfunction "INL_7") (pintype "passive"))
    )
    (net (code "64") (name "Net-(U5-INR)") (class "Default")
      (node (ref "R28") (pin "1") (pinfunction "1_1") (pintype "passive"))
      (node (ref "U5") (pin "10") (pinfunction "INR_10") (pintype "passive"))
    )
    (net (code "65") (name "Net-(U5-VREF)") (class "Default")
      (node (ref "C30") (pin "1") (pinfunction "1_1") (pintype "passive"))
      (node (ref "U5") (pin "8") (pinfunction "VREF_8") (pintype "passive"))
    )
    (net (code "66") (name "VCC3.0V") (class "Default")
      (node (ref "C48") (pin "1") (pinfunction "1_1") (pintype "passive"))
      (node (ref "C49") (pin "2") (pinfunction "2_2") (pintype "passive"))
      (node (ref "C50") (pin "1") (pinfunction "1_1") (pintype "passive"))
      (node (ref "R23") (pin "2") (pinfunction "2_2") (pintype "passive"))
      (node (ref "U6") (pin "2") (pinfunction "VOUT_2") (pintype "passive"))
    )
    (net (code "67") (name "unconnected-(M1-ADC-Pad2)") (class "Default")
      (node (ref "M1") (pin "2") (pinfunction "ADC_2") (pintype "passive"))
    )
    (net (code "68") (name "unconnected-(M1-EN-Pad3)") (class "Default")
      (node (ref "M1") (pin "3") (pinfunction "EN_3") (pintype "passive"))
    )
    (net (code "69") (name "unconnected-(M1-IO0-Pad12)") (class "Default")
      (node (ref "M1") (pin "12") (pinfunction "IO0_12") (pintype "passive"))
    )
    (net (code "70") (name "unconnected-(M1-IO2-Pad11)") (class "Default")
      (node (ref "M1") (pin "11") (pinfunction "IO2_11") (pintype "passive"))
    )
    (net (code "71") (name "unconnected-(M1-IO4-Pad13)") (class "Default")
      (node (ref "M1") (pin "13") (pinfunction "IO4_13") (pintype "passive"))
    )
    (net (code "72") (name "unconnected-(M1-IO5-Pad14)") (class "Default")
      (node (ref "M1") (pin "14") (pinfunction "IO5_14") (pintype "passive"))
    )
    (net (code "73") (name "unconnected-(M1-IO12-Pad6)") (class "Default")
      (node (ref "M1") (pin "6") (pinfunction "IO12_6") (pintype "passive"))
    )
    (net (code "74") (name "unconnected-(M1-IO13-Pad7)") (class "Default")
      (node (ref "M1") (pin "7") (pinfunction "IO13_7") (pintype "passive"))
    )
    (net (code "75") (name "unconnected-(M1-IO14-Pad5)") (class "Default")
      (node (ref "M1") (pin "5") (pinfunction "IO14_5") (pintype "passive"))
    )
    (net (code "76") (name "unconnected-(M1-IO15-Pad10)") (class "Default")
      (node (ref "M1") (pin "10") (pinfunction "IO15_10") (pintype "passive"))
    )
    (net (code "77") (name "unconnected-(M1-IO16-Pad4)") (class "Default")
      (node (ref "M1") (pin "4") (pinfunction "IO16_4") (pintype "passive"))
    )
    (net (code "78") (name "unconnected-(M1-RST-Pad1)") (class "Default")
      (node (ref "M1") (pin "1") (pinfunction "RST_1") (pintype "passive"))
    )
    (net (code "79") (name "unconnected-(TF CARD-CDN-Pad9)") (class "Default")
      (node (ref "TF CARD") (pin "9") (pinfunction "CDN_9") (pintype "passive+no_connect"))
    )
    (net (code "80") (name "unconnected-(U2-R2IN-Pad8)") (class "Default")
      (node (ref "U2") (pin "8") (pinfunction "R2IN_8") (pintype "input"))
    )
    (net (code "81") (name "unconnected-(U2-R2OUT-Pad9)") (class "Default")
      (node (ref "U2") (pin "9") (pinfunction "R2OUT_9") (pintype "output"))
    )
    (net (code "82") (name "unconnected-(U2-T2IN-Pad10)") (class "Default")
      (node (ref "U2") (pin "10") (pinfunction "T2IN_10") (pintype "input"))
    )
    (net (code "83") (name "unconnected-(U2-T2OUT-Pad7)") (class "Default")
      (node (ref "U2") (pin "7") (pinfunction "T2OUT_7") (pintype "output"))
    )
    (net (code "84") (name "unconnected-(USB1-Pad4)") (class "Default")
      (node (ref "USB1") (pin "4") (pinfunction "4_4") (pintype "passive"))
    )
  )
)
